# M162B.net
KiCad netlist of a schematic drawn in EAGLE
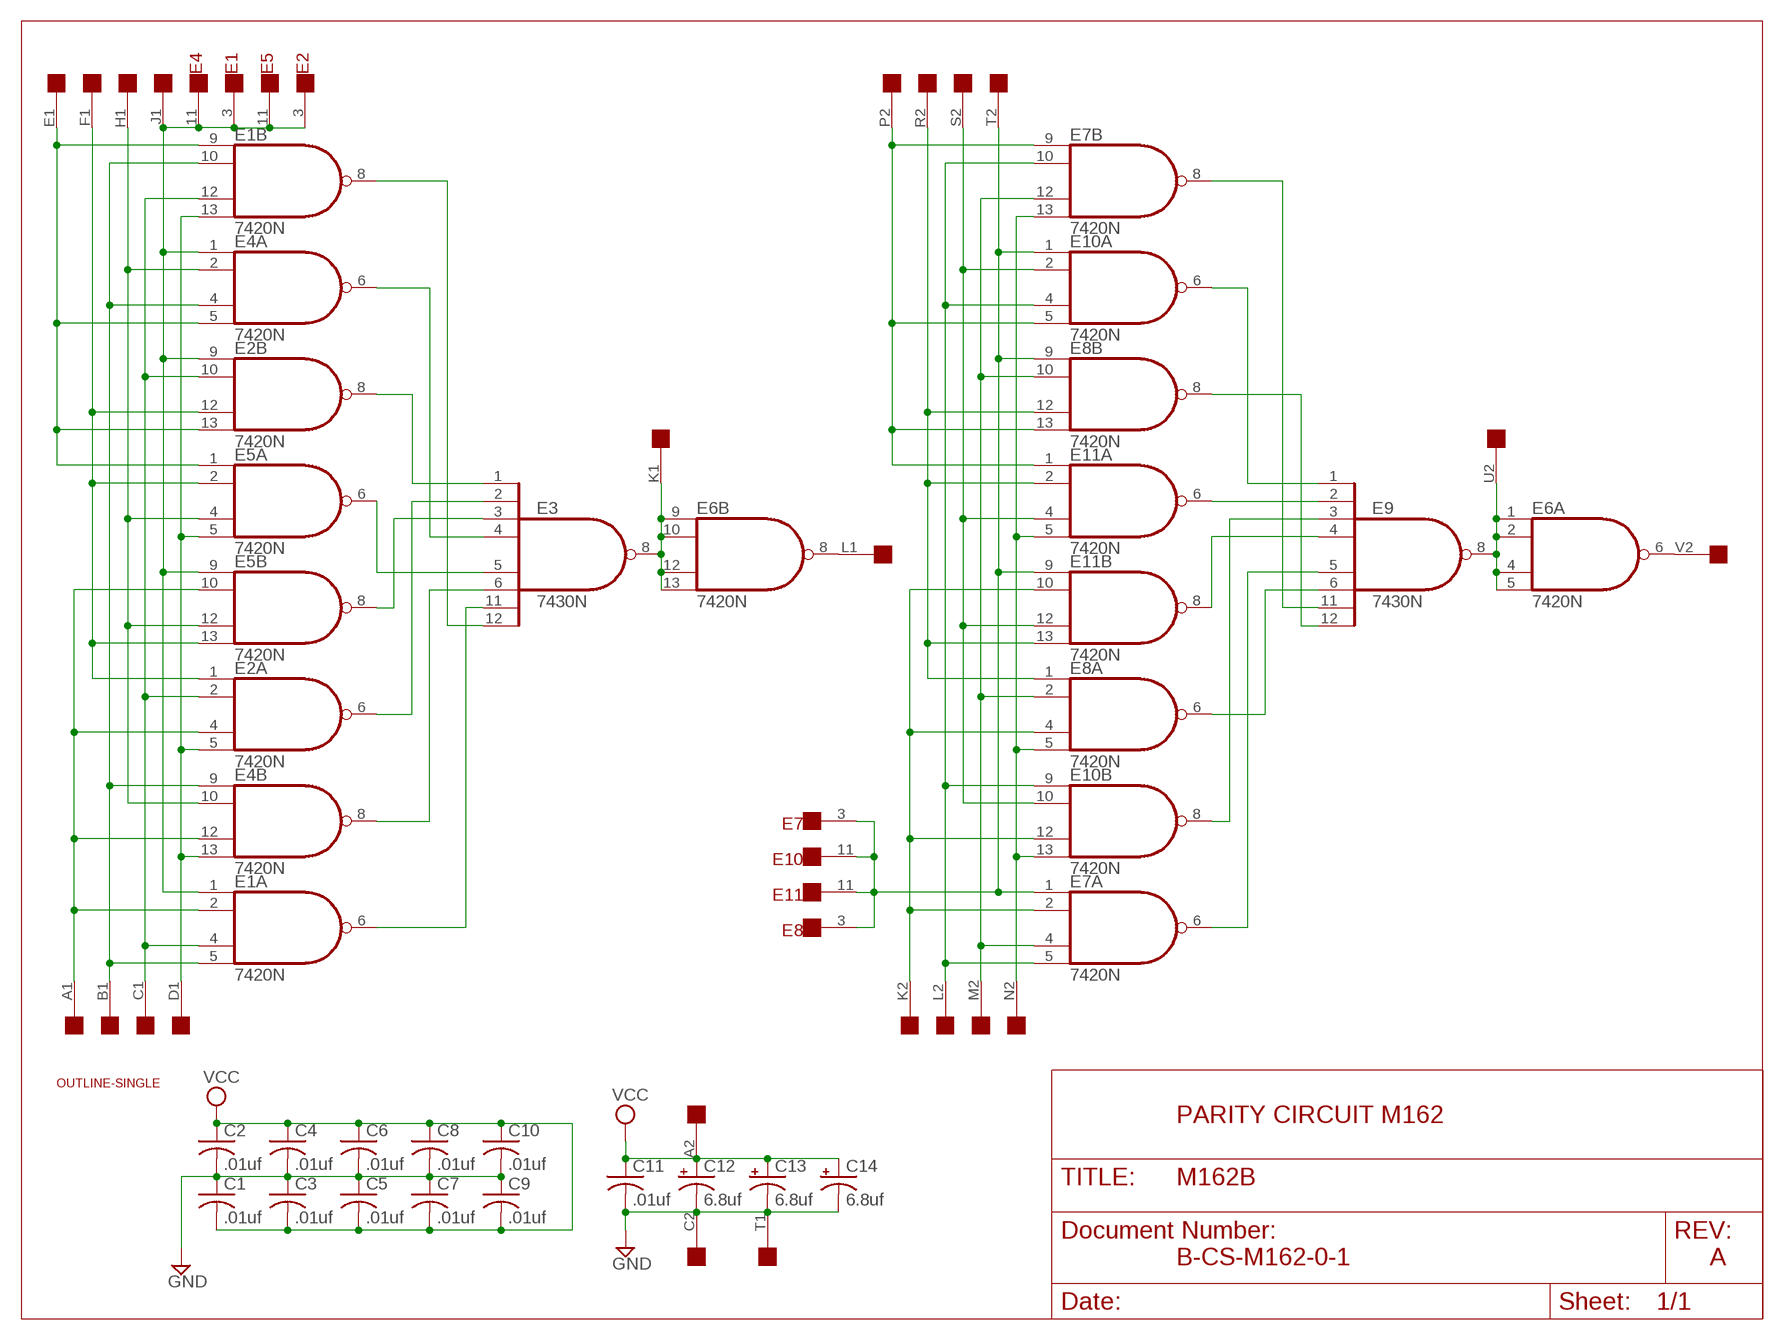
[diagram p0: schematic, sheet 1]

(export (version "E")
  (design (tool "Eeschema 10.0.6"))
  (components
    (comp (ref "C1")
      (value ".01uf")
      (footprint "eagle-import:C050-025X075")
      (libsource (lib "eagle-import") (part "C-US050-025X075"))
    )
    (comp (ref "C2")
      (value ".01uf")
      (footprint "eagle-import:C050-025X075")
      (libsource (lib "eagle-import") (part "C-US050-025X075"))
    )
    (comp (ref "C3")
      (value ".01uf")
      (footprint "eagle-import:C050-025X075")
      (libsource (lib "eagle-import") (part "C-US050-025X075"))
    )
    (comp (ref "C4")
      (value ".01uf")
      (footprint "eagle-import:C050-025X075")
      (libsource (lib "eagle-import") (part "C-US050-025X075"))
    )
    (comp (ref "C5")
      (value ".01uf")
      (footprint "eagle-import:C050-025X075")
      (libsource (lib "eagle-import") (part "C-US050-025X075"))
    )
    (comp (ref "C6")
      (value ".01uf")
      (footprint "eagle-import:C050-025X075")
      (libsource (lib "eagle-import") (part "C-US050-025X075"))
    )
    (comp (ref "C7")
      (value ".01uf")
      (footprint "eagle-import:C050-025X075")
      (libsource (lib "eagle-import") (part "C-US050-025X075"))
    )
    (comp (ref "C8")
      (value ".01uf")
      (footprint "eagle-import:C050-025X075")
      (libsource (lib "eagle-import") (part "C-US050-025X075"))
    )
    (comp (ref "C9")
      (value ".01uf")
      (footprint "eagle-import:C050-025X075")
      (libsource (lib "eagle-import") (part "C-US050-025X075"))
    )
    (comp (ref "C10")
      (value ".01uf")
      (footprint "eagle-import:C050-025X075")
      (libsource (lib "eagle-import") (part "C-US050-025X075"))
    )
    (comp (ref "C11")
      (value ".01uf")
      (footprint "eagle-import:C050-025X075")
      (libsource (lib "eagle-import") (part "C-US050-025X075"))
    )
    (comp (ref "C12")
      (value "6.8uf")
      (footprint "eagle-import:E15-5")
      (libsource (lib "eagle-import") (part "CPOL-USE15-5AXIAL"))
    )
    (comp (ref "C13")
      (value "6.8uf")
      (footprint "eagle-import:E15-5")
      (libsource (lib "eagle-import") (part "CPOL-USE15-5AXIAL"))
    )
    (comp (ref "C14")
      (value "6.8uf")
      (footprint "eagle-import:E15-5")
      (libsource (lib "eagle-import") (part "CPOL-USE15-5AXIAL"))
    )
    (comp (ref "E1")
      (value "7420N")
      (footprint "eagle-import:DIL14")
      (libsource (lib "eagle-import") (part "7420NS"))
    )
    (comp (ref "E2")
      (value "7420N")
      (footprint "eagle-import:DIL14")
      (libsource (lib "eagle-import") (part "7420NS"))
    )
    (comp (ref "E3")
      (value "7430N")
      (footprint "eagle-import:DIL14")
      (libsource (lib "eagle-import") (part "7430N"))
    )
    (comp (ref "E4")
      (value "7420N")
      (footprint "eagle-import:DIL14")
      (libsource (lib "eagle-import") (part "7420NS"))
    )
    (comp (ref "E5")
      (value "7420N")
      (footprint "eagle-import:DIL14")
      (libsource (lib "eagle-import") (part "7420NS"))
    )
    (comp (ref "E6")
      (value "7420N")
      (footprint "eagle-import:DIL14")
      (libsource (lib "eagle-import") (part "7420NS"))
    )
    (comp (ref "E7")
      (value "7420N")
      (footprint "eagle-import:DIL14")
      (libsource (lib "eagle-import") (part "7420NS"))
    )
    (comp (ref "E8")
      (value "7420N")
      (footprint "eagle-import:DIL14")
      (libsource (lib "eagle-import") (part "7420NS"))
    )
    (comp (ref "E9")
      (value "7430N")
      (footprint "eagle-import:DIL14")
      (libsource (lib "eagle-import") (part "7430N"))
    )
    (comp (ref "E10")
      (value "7420N")
      (footprint "eagle-import:DIL14")
      (libsource (lib "eagle-import") (part "7420NS"))
    )
    (comp (ref "E11")
      (value "7420N")
      (footprint "eagle-import:DIL14")
      (libsource (lib "eagle-import") (part "7420NS"))
    )
    (comp (ref "U$1")
      (value "OUTLINE-SINGLE")
      (footprint "eagle-import:SINGLE")
      (libsource (lib "eagle-import") (part "OUTLINE-SINGLE"))
    )
    (comp (ref "U$2")
      (value "EDGE-2CONNECTOR")
      (footprint "eagle-import:EDGE-CON2")
      (libsource (lib "eagle-import") (part "EDGE-2CONNECTOR"))
    )
  )
  (nets
    (net (code "1") (name "GND") (class "Default")
      (node (ref "C1") (pin "1") (pinfunction "1_1") (pintype "passive"))
      (node (ref "C10") (pin "2") (pinfunction "2_2") (pintype "passive"))
      (node (ref "C11") (pin "2") (pinfunction "2_2") (pintype "passive"))
      (node (ref "C12") (pin "-") (pinfunction "-_-") (pintype "passive"))
      (node (ref "C13") (pin "-") (pinfunction "-_-") (pintype "passive"))
      (node (ref "C14") (pin "-") (pinfunction "-_-") (pintype "passive"))
      (node (ref "C2") (pin "2") (pinfunction "2_2") (pintype "passive"))
      (node (ref "C3") (pin "1") (pinfunction "1_1") (pintype "passive"))
      (node (ref "C4") (pin "2") (pinfunction "2_2") (pintype "passive"))
      (node (ref "C5") (pin "1") (pinfunction "1_1") (pintype "passive"))
      (node (ref "C6") (pin "2") (pinfunction "2_2") (pintype "passive"))
      (node (ref "C7") (pin "1") (pinfunction "1_1") (pintype "passive"))
      (node (ref "C8") (pin "2") (pinfunction "2_2") (pintype "passive"))
      (node (ref "C9") (pin "1") (pinfunction "1_1") (pintype "passive"))
      (node (ref "U$2") (pin "C2") (pinfunction "1_C2") (pintype "bidirectional"))
      (node (ref "U$2") (pin "T1") (pinfunction "1_T1") (pintype "bidirectional"))
    )
    (net (code "2") (name "Net-(E1B-NC)") (class "Default")
      (node (ref "E1") (pin "1") (pinfunction "I0_1") (pintype "input"))
      (node (ref "E1") (pin "3") (pinfunction "NC_3") (pintype "passive"))
      (node (ref "E2") (pin "3") (pinfunction "NC_3") (pintype "passive"))
      (node (ref "E2") (pin "9") (pinfunction "I0_9") (pintype "input"))
      (node (ref "E4") (pin "1") (pinfunction "I0_1") (pintype "input"))
      (node (ref "E4") (pin "11") (pinfunction "NC_11") (pintype "passive"))
      (node (ref "E5") (pin "11") (pinfunction "NC_11") (pintype "passive"))
      (node (ref "E5") (pin "9") (pinfunction "I0_9") (pintype "input"))
      (node (ref "U$2") (pin "J1") (pinfunction "1_J1") (pintype "bidirectional"))
    )
    (net (code "3") (name "Net-(E1C-I1)") (class "Default")
      (node (ref "E1") (pin "2") (pinfunction "I1_2") (pintype "input"))
      (node (ref "E2") (pin "4") (pinfunction "I2_4") (pintype "input"))
      (node (ref "E4") (pin "12") (pinfunction "I2_12") (pintype "input"))
      (node (ref "E5") (pin "10") (pinfunction "I1_10") (pintype "input"))
      (node (ref "U$2") (pin "A1") (pinfunction "1_A1") (pintype "bidirectional"))
    )
    (net (code "4") (name "Net-(E1C-I2)") (class "Default")
      (node (ref "E1") (pin "12") (pinfunction "I2_12") (pintype "input"))
      (node (ref "E1") (pin "4") (pinfunction "I2_4") (pintype "input"))
      (node (ref "E2") (pin "10") (pinfunction "I1_10") (pintype "input"))
      (node (ref "E2") (pin "2") (pinfunction "I1_2") (pintype "input"))
      (node (ref "U$2") (pin "C1") (pinfunction "1_C1") (pintype "bidirectional"))
    )
    (net (code "5") (name "Net-(E1C-I3)") (class "Default")
      (node (ref "E1") (pin "10") (pinfunction "I1_10") (pintype "input"))
      (node (ref "E1") (pin "5") (pinfunction "I3_5") (pintype "input"))
      (node (ref "E4") (pin "4") (pinfunction "I2_4") (pintype "input"))
      (node (ref "E4") (pin "9") (pinfunction "I0_9") (pintype "input"))
      (node (ref "U$2") (pin "B1") (pinfunction "1_B1") (pintype "bidirectional"))
    )
    (net (code "6") (name "Net-(E1C-O)") (class "Default")
      (node (ref "E1") (pin "6") (pinfunction "O_6") (pintype "output"))
      (node (ref "E3") (pin "11") (pinfunction "I6_11") (pintype "input"))
    )
    (net (code "7") (name "Net-(E1D-I0)") (class "Default")
      (node (ref "E1") (pin "9") (pinfunction "I0_9") (pintype "input"))
      (node (ref "E2") (pin "13") (pinfunction "I3_13") (pintype "input"))
      (node (ref "E4") (pin "5") (pinfunction "I3_5") (pintype "input"))
      (node (ref "E5") (pin "1") (pinfunction "I0_1") (pintype "input"))
      (node (ref "U$2") (pin "E1") (pinfunction "1_E1") (pintype "bidirectional"))
    )
    (net (code "8") (name "Net-(E1D-I3)") (class "Default")
      (node (ref "E1") (pin "13") (pinfunction "I3_13") (pintype "input"))
      (node (ref "E2") (pin "5") (pinfunction "I3_5") (pintype "input"))
      (node (ref "E4") (pin "13") (pinfunction "I3_13") (pintype "input"))
      (node (ref "E5") (pin "5") (pinfunction "I3_5") (pintype "input"))
      (node (ref "U$2") (pin "D1") (pinfunction "1_D1") (pintype "bidirectional"))
    )
    (net (code "9") (name "Net-(E1D-O)") (class "Default")
      (node (ref "E1") (pin "8") (pinfunction "O_8") (pintype "output"))
      (node (ref "E3") (pin "12") (pinfunction "I7_12") (pintype "input"))
    )
    (net (code "10") (name "Net-(E2C-I0)") (class "Default")
      (node (ref "E2") (pin "1") (pinfunction "I0_1") (pintype "input"))
      (node (ref "E2") (pin "12") (pinfunction "I2_12") (pintype "input"))
      (node (ref "E5") (pin "13") (pinfunction "I3_13") (pintype "input"))
      (node (ref "E5") (pin "2") (pinfunction "I1_2") (pintype "input"))
      (node (ref "U$2") (pin "F1") (pinfunction "1_F1") (pintype "bidirectional"))
    )
    (net (code "11") (name "Net-(E2C-O)") (class "Default")
      (node (ref "E2") (pin "6") (pinfunction "O_6") (pintype "output"))
      (node (ref "E3") (pin "2") (pinfunction "I1_2") (pintype "input"))
    )
    (net (code "12") (name "Net-(E2D-O)") (class "Default")
      (node (ref "E2") (pin "8") (pinfunction "O_8") (pintype "output"))
      (node (ref "E3") (pin "1") (pinfunction "I0_1") (pintype "input"))
    )
    (net (code "13") (name "Net-(E3A-I2)") (class "Default")
      (node (ref "E3") (pin "3") (pinfunction "I2_3") (pintype "input"))
      (node (ref "E5") (pin "8") (pinfunction "O_8") (pintype "output"))
    )
    (net (code "14") (name "Net-(E3A-I3)") (class "Default")
      (node (ref "E3") (pin "4") (pinfunction "I3_4") (pintype "input"))
      (node (ref "E4") (pin "6") (pinfunction "O_6") (pintype "output"))
    )
    (net (code "15") (name "Net-(E3A-I4)") (class "Default")
      (node (ref "E3") (pin "5") (pinfunction "I4_5") (pintype "input"))
      (node (ref "E5") (pin "6") (pinfunction "O_6") (pintype "output"))
    )
    (net (code "16") (name "Net-(E3A-I5)") (class "Default")
      (node (ref "E3") (pin "6") (pinfunction "I5_6") (pintype "input"))
      (node (ref "E4") (pin "8") (pinfunction "O_8") (pintype "output"))
    )
    (net (code "17") (name "Net-(E3A-O)") (class "Default")
      (node (ref "E3") (pin "8") (pinfunction "O_8") (pintype "output"))
      (node (ref "E6") (pin "10") (pinfunction "I1_10") (pintype "input"))
      (node (ref "E6") (pin "12") (pinfunction "I2_12") (pintype "input"))
      (node (ref "E6") (pin "13") (pinfunction "I3_13") (pintype "input"))
      (node (ref "E6") (pin "9") (pinfunction "I0_9") (pintype "input"))
      (node (ref "U$2") (pin "K1") (pinfunction "1_K1") (pintype "bidirectional"))
    )
    (net (code "18") (name "Net-(E4C-I1)") (class "Default")
      (node (ref "E4") (pin "10") (pinfunction "I1_10") (pintype "input"))
      (node (ref "E4") (pin "2") (pinfunction "I1_2") (pintype "input"))
      (node (ref "E5") (pin "12") (pinfunction "I2_12") (pintype "input"))
      (node (ref "E5") (pin "4") (pinfunction "I2_4") (pintype "input"))
      (node (ref "U$2") (pin "H1") (pinfunction "1_H1") (pintype "bidirectional"))
    )
    (net (code "19") (name "Net-(E6C-I0)") (class "Default")
      (node (ref "E6") (pin "1") (pinfunction "I0_1") (pintype "input"))
      (node (ref "E6") (pin "2") (pinfunction "I1_2") (pintype "input"))
      (node (ref "E6") (pin "4") (pinfunction "I2_4") (pintype "input"))
      (node (ref "E6") (pin "5") (pinfunction "I3_5") (pintype "input"))
      (node (ref "E9") (pin "8") (pinfunction "O_8") (pintype "output"))
      (node (ref "U$2") (pin "U2") (pinfunction "1_U2") (pintype "bidirectional"))
    )
    (net (code "20") (name "Net-(E6C-O)") (class "Default")
      (node (ref "E6") (pin "6") (pinfunction "O_6") (pintype "output"))
      (node (ref "U$2") (pin "V2") (pinfunction "1_V2") (pintype "bidirectional"))
    )
    (net (code "21") (name "Net-(E6D-O)") (class "Default")
      (node (ref "E6") (pin "8") (pinfunction "O_8") (pintype "output"))
      (node (ref "U$2") (pin "L1") (pinfunction "1_L1") (pintype "bidirectional"))
    )
    (net (code "22") (name "Net-(E7C-I2)") (class "Default")
      (node (ref "E7") (pin "12") (pinfunction "I2_12") (pintype "input"))
      (node (ref "E7") (pin "4") (pinfunction "I2_4") (pintype "input"))
      (node (ref "E8") (pin "10") (pinfunction "I1_10") (pintype "input"))
      (node (ref "E8") (pin "2") (pinfunction "I1_2") (pintype "input"))
      (node (ref "U$2") (pin "M2") (pinfunction "1_M2") (pintype "bidirectional"))
    )
    (net (code "23") (name "Net-(E7C-O)") (class "Default")
      (node (ref "E7") (pin "6") (pinfunction "O_6") (pintype "output"))
      (node (ref "E9") (pin "5") (pinfunction "I4_5") (pintype "input"))
    )
    (net (code "24") (name "Net-(E7D-O)") (class "Default")
      (node (ref "E7") (pin "8") (pinfunction "O_8") (pintype "output"))
      (node (ref "E9") (pin "11") (pinfunction "I6_11") (pintype "input"))
    )
    (net (code "25") (name "Net-(E8C-O)") (class "Default")
      (node (ref "E8") (pin "6") (pinfunction "O_6") (pintype "output"))
      (node (ref "E9") (pin "6") (pinfunction "I5_6") (pintype "input"))
    )
    (net (code "26") (name "Net-(E8D-O)") (class "Default")
      (node (ref "E8") (pin "8") (pinfunction "O_8") (pintype "output"))
      (node (ref "E9") (pin "12") (pinfunction "I7_12") (pintype "input"))
    )
    (net (code "27") (name "Net-(E10A-NC)") (class "Default")
      (node (ref "E10") (pin "1") (pinfunction "I0_1") (pintype "input"))
      (node (ref "E10") (pin "11") (pinfunction "NC_11") (pintype "passive"))
      (node (ref "E11") (pin "11") (pinfunction "NC_11") (pintype "passive"))
      (node (ref "E11") (pin "9") (pinfunction "I0_9") (pintype "input"))
      (node (ref "E7") (pin "1") (pinfunction "I0_1") (pintype "input"))
      (node (ref "E7") (pin "3") (pinfunction "NC_3") (pintype "passive"))
      (node (ref "E8") (pin "3") (pinfunction "NC_3") (pintype "passive"))
      (node (ref "E8") (pin "9") (pinfunction "I0_9") (pintype "input"))
      (node (ref "U$2") (pin "T2") (pinfunction "1_T2") (pintype "bidirectional"))
    )
    (net (code "28") (name "Net-(E10C-I1)") (class "Default")
      (node (ref "E10") (pin "10") (pinfunction "I1_10") (pintype "input"))
      (node (ref "E10") (pin "2") (pinfunction "I1_2") (pintype "input"))
      (node (ref "E11") (pin "12") (pinfunction "I2_12") (pintype "input"))
      (node (ref "E11") (pin "4") (pinfunction "I2_4") (pintype "input"))
      (node (ref "U$2") (pin "S2") (pinfunction "1_S2") (pintype "bidirectional"))
    )
    (net (code "29") (name "Net-(E10C-I2)") (class "Default")
      (node (ref "E10") (pin "4") (pinfunction "I2_4") (pintype "input"))
      (node (ref "E10") (pin "9") (pinfunction "I0_9") (pintype "input"))
      (node (ref "E7") (pin "10") (pinfunction "I1_10") (pintype "input"))
      (node (ref "E7") (pin "5") (pinfunction "I3_5") (pintype "input"))
      (node (ref "U$2") (pin "L2") (pinfunction "1_L2") (pintype "bidirectional"))
    )
    (net (code "30") (name "Net-(E10C-I3)") (class "Default")
      (node (ref "E10") (pin "5") (pinfunction "I3_5") (pintype "input"))
      (node (ref "E11") (pin "1") (pinfunction "I0_1") (pintype "input"))
      (node (ref "E7") (pin "9") (pinfunction "I0_9") (pintype "input"))
      (node (ref "E8") (pin "13") (pinfunction "I3_13") (pintype "input"))
      (node (ref "U$2") (pin "P2") (pinfunction "1_P2") (pintype "bidirectional"))
    )
    (net (code "31") (name "Net-(E10C-O)") (class "Default")
      (node (ref "E10") (pin "6") (pinfunction "O_6") (pintype "output"))
      (node (ref "E9") (pin "1") (pinfunction "I0_1") (pintype "input"))
    )
    (net (code "32") (name "Net-(E10D-I2)") (class "Default")
      (node (ref "E10") (pin "12") (pinfunction "I2_12") (pintype "input"))
      (node (ref "E11") (pin "10") (pinfunction "I1_10") (pintype "input"))
      (node (ref "E7") (pin "2") (pinfunction "I1_2") (pintype "input"))
      (node (ref "E8") (pin "4") (pinfunction "I2_4") (pintype "input"))
      (node (ref "U$2") (pin "K2") (pinfunction "1_K2") (pintype "bidirectional"))
    )
    (net (code "33") (name "Net-(E10D-I3)") (class "Default")
      (node (ref "E10") (pin "13") (pinfunction "I3_13") (pintype "input"))
      (node (ref "E11") (pin "5") (pinfunction "I3_5") (pintype "input"))
      (node (ref "E7") (pin "13") (pinfunction "I3_13") (pintype "input"))
      (node (ref "E8") (pin "5") (pinfunction "I3_5") (pintype "input"))
      (node (ref "U$2") (pin "N2") (pinfunction "1_N2") (pintype "bidirectional"))
    )
    (net (code "34") (name "Net-(E10D-O)") (class "Default")
      (node (ref "E10") (pin "8") (pinfunction "O_8") (pintype "output"))
      (node (ref "E9") (pin "3") (pinfunction "I2_3") (pintype "input"))
    )
    (net (code "35") (name "Net-(E11C-I1)") (class "Default")
      (node (ref "E11") (pin "13") (pinfunction "I3_13") (pintype "input"))
      (node (ref "E11") (pin "2") (pinfunction "I1_2") (pintype "input"))
      (node (ref "E8") (pin "1") (pinfunction "I0_1") (pintype "input"))
      (node (ref "E8") (pin "12") (pinfunction "I2_12") (pintype "input"))
      (node (ref "U$2") (pin "R2") (pinfunction "1_R2") (pintype "bidirectional"))
    )
    (net (code "36") (name "Net-(E11C-O)") (class "Default")
      (node (ref "E11") (pin "6") (pinfunction "O_6") (pintype "output"))
      (node (ref "E9") (pin "2") (pinfunction "I1_2") (pintype "input"))
    )
    (net (code "37") (name "Net-(E11D-O)") (class "Default")
      (node (ref "E11") (pin "8") (pinfunction "O_8") (pintype "output"))
      (node (ref "E9") (pin "4") (pinfunction "I3_4") (pintype "input"))
    )
    (net (code "38") (name "VCC") (class "Default")
      (node (ref "C1") (pin "2") (pinfunction "2_2") (pintype "passive"))
      (node (ref "C10") (pin "1") (pinfunction "1_1") (pintype "passive"))
      (node (ref "C11") (pin "1") (pinfunction "1_1") (pintype "passive"))
      (node (ref "C12") (pin "+") (pinfunction "+_+") (pintype "passive"))
      (node (ref "C13") (pin "+") (pinfunction "+_+") (pintype "passive"))
      (node (ref "C14") (pin "+") (pinfunction "+_+") (pintype "passive"))
      (node (ref "C2") (pin "1") (pinfunction "1_1") (pintype "passive"))
      (node (ref "C3") (pin "2") (pinfunction "2_2") (pintype "passive"))
      (node (ref "C4") (pin "1") (pinfunction "1_1") (pintype "passive"))
      (node (ref "C5") (pin "2") (pinfunction "2_2") (pintype "passive"))
      (node (ref "C6") (pin "1") (pinfunction "1_1") (pintype "passive"))
      (node (ref "C7") (pin "2") (pinfunction "2_2") (pintype "passive"))
      (node (ref "C8") (pin "1") (pinfunction "1_1") (pintype "passive"))
      (node (ref "C9") (pin "2") (pinfunction "2_2") (pintype "passive"))
      (node (ref "U$2") (pin "A2") (pinfunction "1_A2") (pintype "bidirectional"))
    )
  )
)
